# ioboard.net
KiCad netlist of a schematic drawn in EAGLE
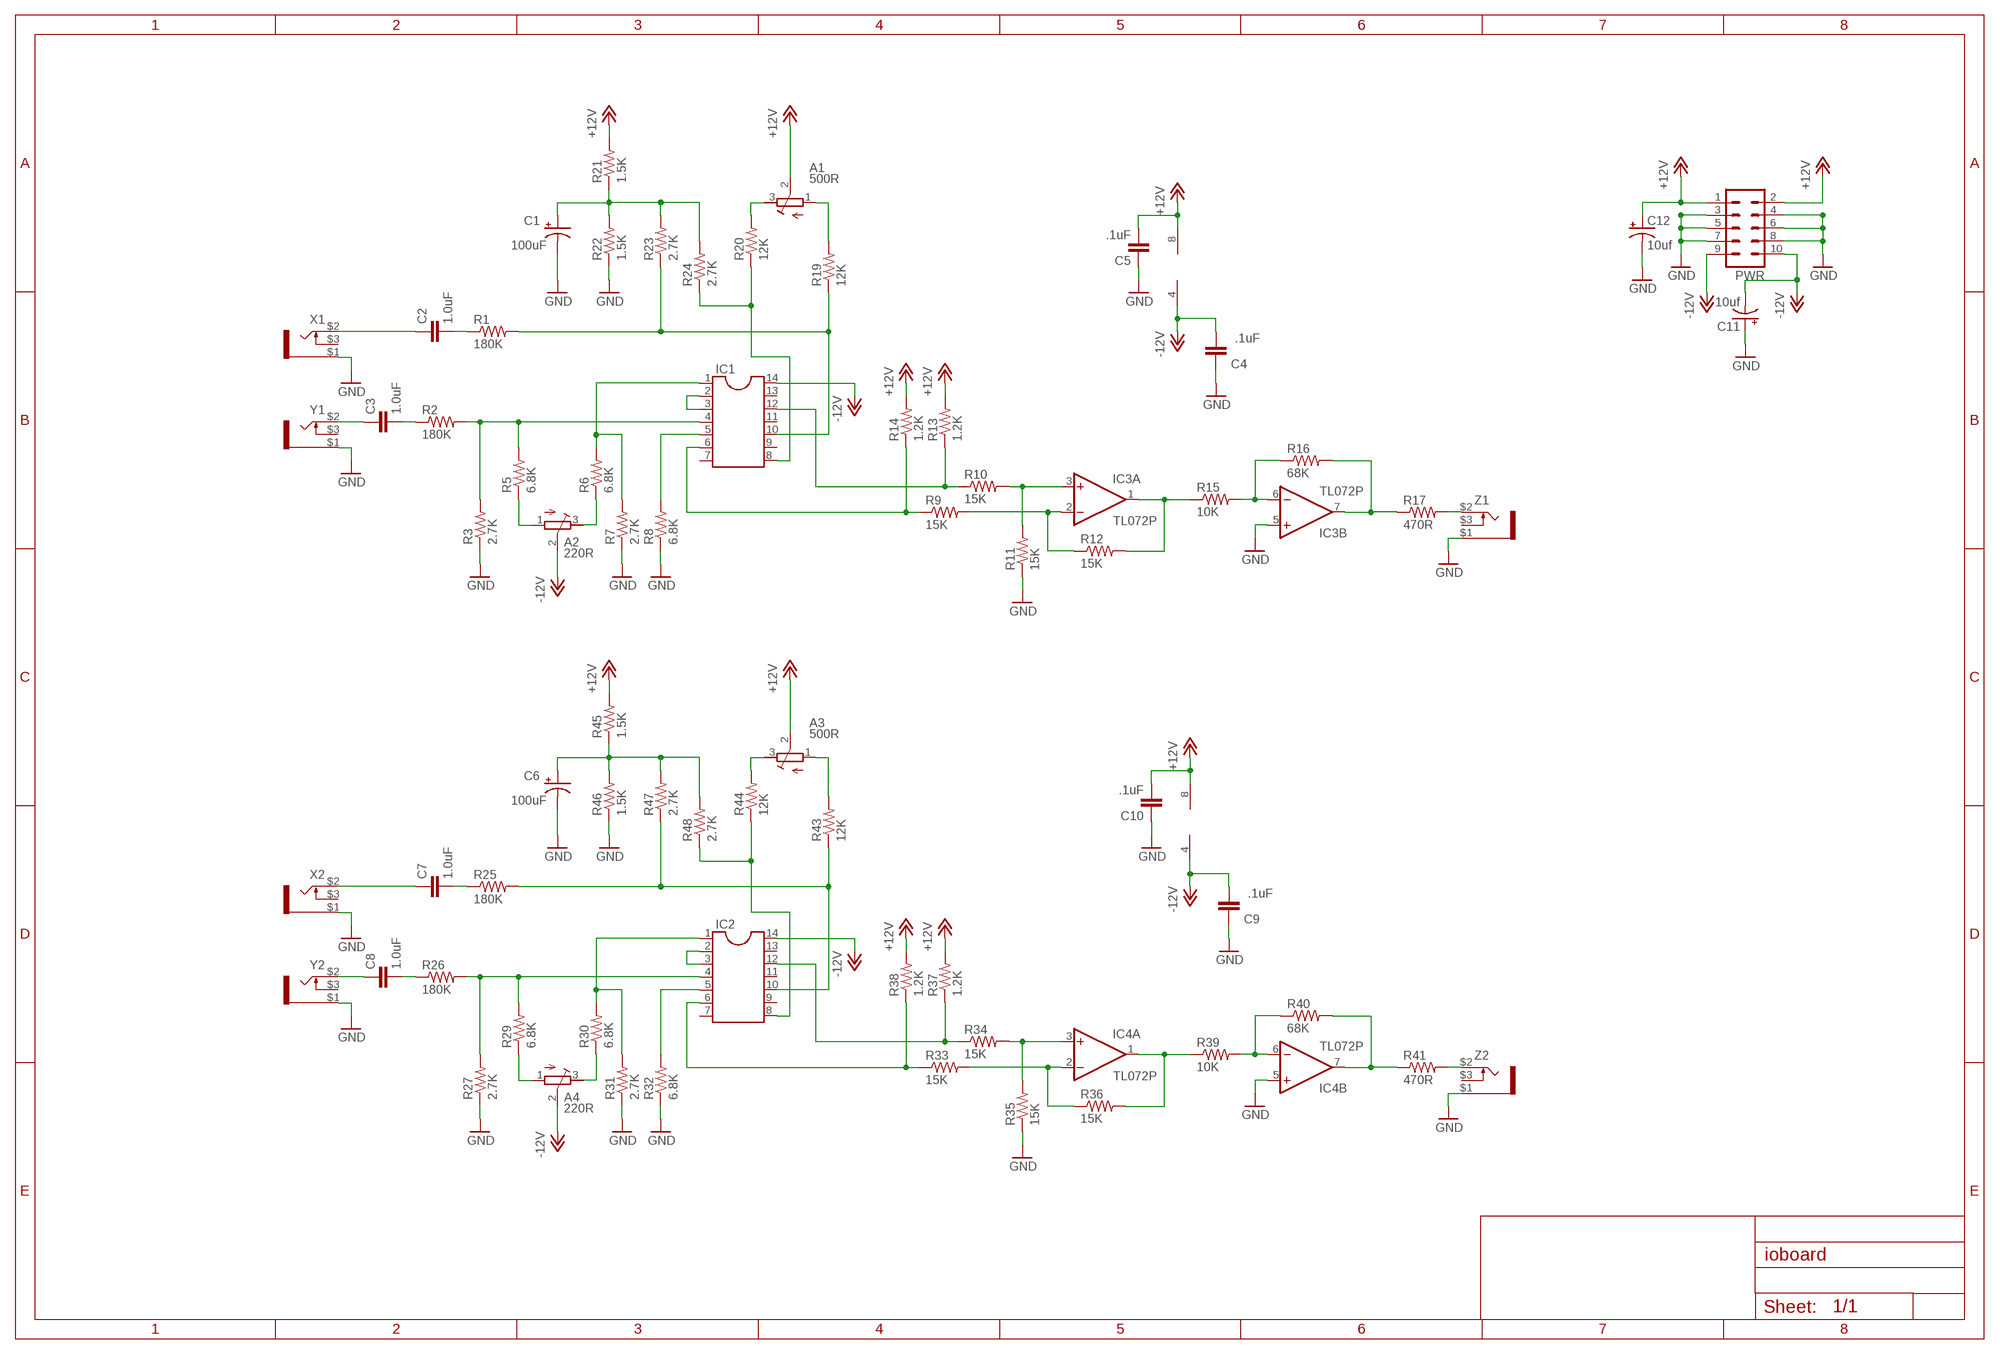
[diagram p0: schematic, sheet 1]

(export (version "E")
  (design (tool "Eeschema 10.0.6"))
  (components
    (comp (ref "A1")
      (value "500R")
      (footprint "eagle-import:RTRIM3296W")
      (libsource (lib "eagle-import") (part "R-TRIMM3296W"))
    )
    (comp (ref "A2")
      (value "220R")
      (footprint "eagle-import:RTRIM3296W")
      (libsource (lib "eagle-import") (part "R-TRIMM3296W"))
    )
    (comp (ref "A3")
      (value "500R")
      (footprint "eagle-import:RTRIM3296W")
      (libsource (lib "eagle-import") (part "R-TRIMM3296W"))
    )
    (comp (ref "A4")
      (value "220R")
      (footprint "eagle-import:RTRIM3296W")
      (libsource (lib "eagle-import") (part "R-TRIMM3296W"))
    )
    (comp (ref "C1")
      (value "100uF")
      (footprint "eagle-import:E2,5-6")
      (libsource (lib "eagle-import") (part "resistor_348_CPOL-USE2.5-6"))
    )
    (comp (ref "C2")
      (value "1.0uF")
      (footprint "eagle-import:C050-024X044")
      (libsource (lib "eagle-import") (part "C-EU050-024X044"))
    )
    (comp (ref "C3")
      (value "1.0uF")
      (footprint "eagle-import:C050-024X044")
      (libsource (lib "eagle-import") (part "C-EU050-024X044"))
    )
    (comp (ref "C4")
      (value ".1uF")
      (footprint "eagle-import:C050-024X044")
      (libsource (lib "eagle-import") (part "C-EU050-024X044"))
    )
    (comp (ref "C5")
      (value ".1uF")
      (footprint "eagle-import:C050-024X044")
      (libsource (lib "eagle-import") (part "C-EU050-024X044"))
    )
    (comp (ref "C6")
      (value "100uF")
      (footprint "eagle-import:E2,5-6")
      (libsource (lib "eagle-import") (part "resistor_348_CPOL-USE2.5-6"))
    )
    (comp (ref "C7")
      (value "1.0uF")
      (footprint "eagle-import:C050-024X044")
      (libsource (lib "eagle-import") (part "C-EU050-024X044"))
    )
    (comp (ref "C8")
      (value "1.0uF")
      (footprint "eagle-import:C050-024X044")
      (libsource (lib "eagle-import") (part "C-EU050-024X044"))
    )
    (comp (ref "C9")
      (value ".1uF")
      (footprint "eagle-import:C050-024X044")
      (libsource (lib "eagle-import") (part "C-EU050-024X044"))
    )
    (comp (ref "C10")
      (value ".1uF")
      (footprint "eagle-import:C050-024X044")
      (libsource (lib "eagle-import") (part "C-EU050-024X044"))
    )
    (comp (ref "C11")
      (value "10uf")
      (footprint "eagle-import:E2,5-5")
      (libsource (lib "eagle-import") (part "CPOL-USE2.5-5"))
    )
    (comp (ref "C12")
      (value "10uf")
      (footprint "eagle-import:E2,5-5")
      (libsource (lib "eagle-import") (part "CPOL-USE2.5-5"))
    )
    (comp (ref "IC1")
      (value "LM1496")
      (footprint "eagle-import:LM1496")
      (libsource (lib "eagle-import") (part "LM1496"))
    )
    (comp (ref "IC2")
      (value "LM1496")
      (footprint "eagle-import:LM1496")
      (libsource (lib "eagle-import") (part "LM1496"))
    )
    (comp (ref "IC3")
      (value "TL072P")
      (footprint "eagle-import:DIL08")
      (libsource (lib "eagle-import") (part "TL072P"))
    )
    (comp (ref "IC4")
      (value "TL072P")
      (footprint "eagle-import:DIL08")
      (libsource (lib "eagle-import") (part "TL072P"))
    )
    (comp (ref "PWR")
      (value "ML10")
      (footprint "eagle-import:ML10")
      (libsource (lib "eagle-import") (part "ML10"))
    )
    (comp (ref "R1")
      (value "180K")
      (footprint "eagle-import:0207_7")
      (libsource (lib "eagle-import") (part "R-US_0207/7"))
    )
    (comp (ref "R2")
      (value "180K")
      (footprint "eagle-import:0207_7")
      (libsource (lib "eagle-import") (part "R-US_0207/7"))
    )
    (comp (ref "R3")
      (value "2.7K")
      (footprint "eagle-import:0207_7")
      (libsource (lib "eagle-import") (part "R-US_0207/7"))
    )
    (comp (ref "R5")
      (value "6.8K")
      (footprint "eagle-import:0207_7")
      (libsource (lib "eagle-import") (part "R-US_0207/7"))
    )
    (comp (ref "R6")
      (value "6.8K")
      (footprint "eagle-import:0207_7")
      (libsource (lib "eagle-import") (part "R-US_0207/7"))
    )
    (comp (ref "R7")
      (value "2.7K")
      (footprint "eagle-import:0207_7")
      (libsource (lib "eagle-import") (part "R-US_0207/7"))
    )
    (comp (ref "R8")
      (value "6.8K")
      (footprint "eagle-import:0207_7")
      (libsource (lib "eagle-import") (part "R-US_0207/7"))
    )
    (comp (ref "R9")
      (value "15K")
      (footprint "eagle-import:0207_7")
      (libsource (lib "eagle-import") (part "R-US_0207/7"))
    )
    (comp (ref "R10")
      (value "15K")
      (footprint "eagle-import:0207_7")
      (libsource (lib "eagle-import") (part "R-US_0207/7"))
    )
    (comp (ref "R11")
      (value "15K")
      (footprint "eagle-import:0207_7")
      (libsource (lib "eagle-import") (part "R-US_0207/7"))
    )
    (comp (ref "R12")
      (value "15K")
      (footprint "eagle-import:0207_7")
      (libsource (lib "eagle-import") (part "R-US_0207/7"))
    )
    (comp (ref "R13")
      (value "1.2K")
      (footprint "eagle-import:0207_7")
      (libsource (lib "eagle-import") (part "R-US_0207/7"))
    )
    (comp (ref "R14")
      (value "1.2K")
      (footprint "eagle-import:0207_7")
      (libsource (lib "eagle-import") (part "R-US_0207/7"))
    )
    (comp (ref "R15")
      (value "10K")
      (footprint "eagle-import:0207_7")
      (libsource (lib "eagle-import") (part "R-US_0207/7"))
    )
    (comp (ref "R16")
      (value "68K")
      (footprint "eagle-import:0207_7")
      (libsource (lib "eagle-import") (part "R-US_0207/7"))
    )
    (comp (ref "R17")
      (value "470R")
      (footprint "eagle-import:0207_7")
      (libsource (lib "eagle-import") (part "R-US_0207/7"))
    )
    (comp (ref "R19")
      (value "12K")
      (footprint "eagle-import:0207_7")
      (libsource (lib "eagle-import") (part "R-US_0207/7"))
    )
    (comp (ref "R20")
      (value "12K")
      (footprint "eagle-import:0207_7")
      (libsource (lib "eagle-import") (part "R-US_0207/7"))
    )
    (comp (ref "R21")
      (value "1.5K")
      (footprint "eagle-import:0207_7")
      (libsource (lib "eagle-import") (part "R-US_0207/7"))
    )
    (comp (ref "R22")
      (value "1.5K")
      (footprint "eagle-import:0207_7")
      (libsource (lib "eagle-import") (part "R-US_0207/7"))
    )
    (comp (ref "R23")
      (value "2.7K")
      (footprint "eagle-import:0207_7")
      (libsource (lib "eagle-import") (part "R-US_0207/7"))
    )
    (comp (ref "R24")
      (value "2.7K")
      (footprint "eagle-import:0207_7")
      (libsource (lib "eagle-import") (part "R-US_0207/7"))
    )
    (comp (ref "R25")
      (value "180K")
      (footprint "eagle-import:0207_7")
      (libsource (lib "eagle-import") (part "R-US_0207/7"))
    )
    (comp (ref "R26")
      (value "180K")
      (footprint "eagle-import:0207_7")
      (libsource (lib "eagle-import") (part "R-US_0207/7"))
    )
    (comp (ref "R27")
      (value "2.7K")
      (footprint "eagle-import:0207_7")
      (libsource (lib "eagle-import") (part "R-US_0207/7"))
    )
    (comp (ref "R29")
      (value "6.8K")
      (footprint "eagle-import:0207_7")
      (libsource (lib "eagle-import") (part "R-US_0207/7"))
    )
    (comp (ref "R30")
      (value "6.8K")
      (footprint "eagle-import:0207_7")
      (libsource (lib "eagle-import") (part "R-US_0207/7"))
    )
    (comp (ref "R31")
      (value "2.7K")
      (footprint "eagle-import:0207_7")
      (libsource (lib "eagle-import") (part "R-US_0207/7"))
    )
    (comp (ref "R32")
      (value "6.8K")
      (footprint "eagle-import:0207_7")
      (libsource (lib "eagle-import") (part "R-US_0207/7"))
    )
    (comp (ref "R33")
      (value "15K")
      (footprint "eagle-import:0207_7")
      (libsource (lib "eagle-import") (part "R-US_0207/7"))
    )
    (comp (ref "R34")
      (value "15K")
      (footprint "eagle-import:0207_7")
      (libsource (lib "eagle-import") (part "R-US_0207/7"))
    )
    (comp (ref "R35")
      (value "15K")
      (footprint "eagle-import:0207_7")
      (libsource (lib "eagle-import") (part "R-US_0207/7"))
    )
    (comp (ref "R36")
      (value "15K")
      (footprint "eagle-import:0207_7")
      (libsource (lib "eagle-import") (part "R-US_0207/7"))
    )
    (comp (ref "R37")
      (value "1.2K")
      (footprint "eagle-import:0207_7")
      (libsource (lib "eagle-import") (part "R-US_0207/7"))
    )
    (comp (ref "R38")
      (value "1.2K")
      (footprint "eagle-import:0207_7")
      (libsource (lib "eagle-import") (part "R-US_0207/7"))
    )
    (comp (ref "R39")
      (value "10K")
      (footprint "eagle-import:0207_7")
      (libsource (lib "eagle-import") (part "R-US_0207/7"))
    )
    (comp (ref "R40")
      (value "68K")
      (footprint "eagle-import:0207_7")
      (libsource (lib "eagle-import") (part "R-US_0207/7"))
    )
    (comp (ref "R41")
      (value "470R")
      (footprint "eagle-import:0207_7")
      (libsource (lib "eagle-import") (part "R-US_0207/7"))
    )
    (comp (ref "R43")
      (value "12K")
      (footprint "eagle-import:0207_7")
      (libsource (lib "eagle-import") (part "R-US_0207/7"))
    )
    (comp (ref "R44")
      (value "12K")
      (footprint "eagle-import:0207_7")
      (libsource (lib "eagle-import") (part "R-US_0207/7"))
    )
    (comp (ref "R45")
      (value "1.5K")
      (footprint "eagle-import:0207_7")
      (libsource (lib "eagle-import") (part "R-US_0207/7"))
    )
    (comp (ref "R46")
      (value "1.5K")
      (footprint "eagle-import:0207_7")
      (libsource (lib "eagle-import") (part "R-US_0207/7"))
    )
    (comp (ref "R47")
      (value "2.7K")
      (footprint "eagle-import:0207_7")
      (libsource (lib "eagle-import") (part "R-US_0207/7"))
    )
    (comp (ref "R48")
      (value "2.7K")
      (footprint "eagle-import:0207_7")
      (libsource (lib "eagle-import") (part "R-US_0207/7"))
    )
    (comp (ref "X1")
      (value "PJ-323PJ-323")
      (footprint "eagle-import:PJ-323")
      (libsource (lib "eagle-import") (part "PJ-323PJ-323"))
    )
    (comp (ref "X2")
      (value "PJ-323PJ-323")
      (footprint "eagle-import:PJ-323")
      (libsource (lib "eagle-import") (part "PJ-323PJ-323"))
    )
    (comp (ref "Y1")
      (value "PJ-323PJ-323")
      (footprint "eagle-import:PJ-323")
      (libsource (lib "eagle-import") (part "PJ-323PJ-323"))
    )
    (comp (ref "Y2")
      (value "PJ-323PJ-323")
      (footprint "eagle-import:PJ-323")
      (libsource (lib "eagle-import") (part "PJ-323PJ-323"))
    )
    (comp (ref "Z1")
      (value "PJ-323PJ-323")
      (footprint "eagle-import:PJ-323")
      (libsource (lib "eagle-import") (part "PJ-323PJ-323"))
    )
    (comp (ref "Z2")
      (value "PJ-323PJ-323")
      (footprint "eagle-import:PJ-323")
      (libsource (lib "eagle-import") (part "PJ-323PJ-323"))
    )
  )
  (nets
    (net (code "1") (name "+12V") (class "Default")
      (node (ref "A1") (pin "2") (pinfunction "S_2") (pintype "passive"))
      (node (ref "A3") (pin "2") (pinfunction "S_2") (pintype "passive"))
      (node (ref "C10") (pin "2") (pinfunction "2_2") (pintype "passive"))
      (node (ref "C12") (pin "+") (pinfunction "+_+") (pintype "passive"))
      (node (ref "C5") (pin "2") (pinfunction "2_2") (pintype "passive"))
      (node (ref "IC3") (pin "8") (pinfunction "V+_8") (pintype "power_in"))
      (node (ref "IC4") (pin "8") (pinfunction "V+_8") (pintype "power_in"))
      (node (ref "PWR") (pin "1") (pinfunction "1_1") (pintype "passive"))
      (node (ref "PWR") (pin "2") (pinfunction "2_2") (pintype "passive"))
      (node (ref "R13") (pin "2") (pinfunction "2_2") (pintype "passive"))
      (node (ref "R14") (pin "2") (pinfunction "2_2") (pintype "passive"))
      (node (ref "R21") (pin "2") (pinfunction "2_2") (pintype "passive"))
      (node (ref "R37") (pin "2") (pinfunction "2_2") (pintype "passive"))
      (node (ref "R38") (pin "2") (pinfunction "2_2") (pintype "passive"))
      (node (ref "R45") (pin "2") (pinfunction "2_2") (pintype "passive"))
    )
    (net (code "2") (name "-12V") (class "Default")
      (node (ref "A2") (pin "2") (pinfunction "S_2") (pintype "passive"))
      (node (ref "A4") (pin "2") (pinfunction "S_2") (pintype "passive"))
      (node (ref "C11") (pin "-") (pinfunction "-_-") (pintype "passive"))
      (node (ref "C4") (pin "2") (pinfunction "2_2") (pintype "passive"))
      (node (ref "C9") (pin "2") (pinfunction "2_2") (pintype "passive"))
      (node (ref "IC1") (pin "14") (pinfunction "14_14") (pintype "passive"))
      (node (ref "IC2") (pin "14") (pinfunction "14_14") (pintype "passive"))
      (node (ref "IC3") (pin "4") (pinfunction "V-_4") (pintype "power_in"))
      (node (ref "IC4") (pin "4") (pinfunction "V-_4") (pintype "power_in"))
      (node (ref "PWR") (pin "10") (pinfunction "10_10") (pintype "passive"))
      (node (ref "PWR") (pin "9") (pinfunction "9_9") (pintype "passive"))
    )
    (net (code "3") (name "GND") (class "Default")
      (node (ref "C1") (pin "-") (pinfunction "-_-") (pintype "passive"))
      (node (ref "C10") (pin "1") (pinfunction "1_1") (pintype "passive"))
      (node (ref "C11") (pin "+") (pinfunction "+_+") (pintype "passive"))
      (node (ref "C12") (pin "-") (pinfunction "-_-") (pintype "passive"))
      (node (ref "C4") (pin "1") (pinfunction "1_1") (pintype "passive"))
      (node (ref "C5") (pin "1") (pinfunction "1_1") (pintype "passive"))
      (node (ref "C6") (pin "-") (pinfunction "-_-") (pintype "passive"))
      (node (ref "C9") (pin "1") (pinfunction "1_1") (pintype "passive"))
      (node (ref "IC3") (pin "5") (pinfunction "+IN_5") (pintype "input"))
      (node (ref "IC4") (pin "5") (pinfunction "+IN_5") (pintype "input"))
      (node (ref "PWR") (pin "3") (pinfunction "3_3") (pintype "passive"))
      (node (ref "PWR") (pin "4") (pinfunction "4_4") (pintype "passive"))
      (node (ref "PWR") (pin "5") (pinfunction "5_5") (pintype "passive"))
      (node (ref "PWR") (pin "6") (pinfunction "6_6") (pintype "passive"))
      (node (ref "PWR") (pin "7") (pinfunction "7_7") (pintype "passive"))
      (node (ref "PWR") (pin "8") (pinfunction "8_8") (pintype "passive"))
      (node (ref "R11") (pin "1") (pinfunction "1_1") (pintype "passive"))
      (node (ref "R22") (pin "1") (pinfunction "1_1") (pintype "passive"))
      (node (ref "R27") (pin "1") (pinfunction "1_1") (pintype "passive"))
      (node (ref "R3") (pin "1") (pinfunction "1_1") (pintype "passive"))
      (node (ref "R31") (pin "1") (pinfunction "1_1") (pintype "passive"))
      (node (ref "R32") (pin "1") (pinfunction "1_1") (pintype "passive"))
      (node (ref "R35") (pin "1") (pinfunction "1_1") (pintype "passive"))
      (node (ref "R46") (pin "1") (pinfunction "1_1") (pintype "passive"))
      (node (ref "R7") (pin "1") (pinfunction "1_1") (pintype "passive"))
      (node (ref "R8") (pin "1") (pinfunction "1_1") (pintype "passive"))
      (node (ref "X1") (pin "$1") (pinfunction "3_$1") (pintype "passive"))
      (node (ref "X2") (pin "$1") (pinfunction "3_$1") (pintype "passive"))
      (node (ref "Y1") (pin "$1") (pinfunction "3_$1") (pintype "passive"))
      (node (ref "Y2") (pin "$1") (pinfunction "3_$1") (pintype "passive"))
      (node (ref "Z1") (pin "$1") (pinfunction "3_$1") (pintype "passive"))
      (node (ref "Z2") (pin "$1") (pinfunction "3_$1") (pintype "passive"))
    )
    (net (code "4") (name "Net-(A1-A)") (class "Default")
      (node (ref "A1") (pin "1") (pinfunction "A_1") (pintype "passive"))
      (node (ref "R19") (pin "2") (pinfunction "2_2") (pintype "passive"))
    )
    (net (code "5") (name "Net-(A1-E)") (class "Default")
      (node (ref "A1") (pin "3") (pinfunction "E_3") (pintype "passive"))
      (node (ref "R20") (pin "2") (pinfunction "2_2") (pintype "passive"))
    )
    (net (code "6") (name "Net-(A2-A)") (class "Default")
      (node (ref "A2") (pin "1") (pinfunction "A_1") (pintype "passive"))
      (node (ref "R5") (pin "1") (pinfunction "1_1") (pintype "passive"))
    )
    (net (code "7") (name "Net-(A2-E)") (class "Default")
      (node (ref "A2") (pin "3") (pinfunction "E_3") (pintype "passive"))
      (node (ref "R6") (pin "1") (pinfunction "1_1") (pintype "passive"))
    )
    (net (code "8") (name "Net-(A3-A)") (class "Default")
      (node (ref "A3") (pin "1") (pinfunction "A_1") (pintype "passive"))
      (node (ref "R43") (pin "2") (pinfunction "2_2") (pintype "passive"))
    )
    (net (code "9") (name "Net-(A3-E)") (class "Default")
      (node (ref "A3") (pin "3") (pinfunction "E_3") (pintype "passive"))
      (node (ref "R44") (pin "2") (pinfunction "2_2") (pintype "passive"))
    )
    (net (code "10") (name "Net-(A4-A)") (class "Default")
      (node (ref "A4") (pin "1") (pinfunction "A_1") (pintype "passive"))
      (node (ref "R29") (pin "1") (pinfunction "1_1") (pintype "passive"))
    )
    (net (code "11") (name "Net-(A4-E)") (class "Default")
      (node (ref "A4") (pin "3") (pinfunction "E_3") (pintype "passive"))
      (node (ref "R30") (pin "1") (pinfunction "1_1") (pintype "passive"))
    )
    (net (code "12") (name "Net-(C1-Pad+)") (class "Default")
      (node (ref "C1") (pin "+") (pinfunction "+_+") (pintype "passive"))
      (node (ref "R21") (pin "1") (pinfunction "1_1") (pintype "passive"))
      (node (ref "R22") (pin "2") (pinfunction "2_2") (pintype "passive"))
      (node (ref "R23") (pin "2") (pinfunction "2_2") (pintype "passive"))
      (node (ref "R24") (pin "2") (pinfunction "2_2") (pintype "passive"))
    )
    (net (code "13") (name "Net-(C2-Pad2)") (class "Default")
      (node (ref "C2") (pin "2") (pinfunction "2_2") (pintype "passive"))
      (node (ref "R1") (pin "1") (pinfunction "1_1") (pintype "passive"))
    )
    (net (code "14") (name "Net-(C3-Pad2)") (class "Default")
      (node (ref "C3") (pin "2") (pinfunction "2_2") (pintype "passive"))
      (node (ref "R2") (pin "1") (pinfunction "1_1") (pintype "passive"))
    )
    (net (code "15") (name "Net-(C6-Pad+)") (class "Default")
      (node (ref "C6") (pin "+") (pinfunction "+_+") (pintype "passive"))
      (node (ref "R45") (pin "1") (pinfunction "1_1") (pintype "passive"))
      (node (ref "R46") (pin "2") (pinfunction "2_2") (pintype "passive"))
      (node (ref "R47") (pin "2") (pinfunction "2_2") (pintype "passive"))
      (node (ref "R48") (pin "2") (pinfunction "2_2") (pintype "passive"))
    )
    (net (code "16") (name "Net-(C7-Pad2)") (class "Default")
      (node (ref "C7") (pin "2") (pinfunction "2_2") (pintype "passive"))
      (node (ref "R25") (pin "1") (pinfunction "1_1") (pintype "passive"))
    )
    (net (code "17") (name "Net-(C8-Pad2)") (class "Default")
      (node (ref "C8") (pin "2") (pinfunction "2_2") (pintype "passive"))
      (node (ref "R26") (pin "1") (pinfunction "1_1") (pintype "passive"))
    )
    (net (code "18") (name "Net-(IC1-Pad1)") (class "Default")
      (node (ref "IC1") (pin "1") (pinfunction "1_1") (pintype "passive"))
      (node (ref "R6") (pin "2") (pinfunction "2_2") (pintype "passive"))
      (node (ref "R7") (pin "2") (pinfunction "2_2") (pintype "passive"))
    )
    (net (code "19") (name "Net-(IC1-Pad2)") (class "Default")
      (node (ref "IC1") (pin "2") (pinfunction "2_2") (pintype "passive"))
      (node (ref "IC1") (pin "3") (pinfunction "3_3") (pintype "passive"))
    )
    (net (code "20") (name "Net-(IC1-Pad4)") (class "Default")
      (node (ref "IC1") (pin "4") (pinfunction "4_4") (pintype "passive"))
      (node (ref "R2") (pin "2") (pinfunction "2_2") (pintype "passive"))
      (node (ref "R3") (pin "2") (pinfunction "2_2") (pintype "passive"))
      (node (ref "R5") (pin "2") (pinfunction "2_2") (pintype "passive"))
    )
    (net (code "21") (name "Net-(IC1-Pad5)") (class "Default")
      (node (ref "IC1") (pin "5") (pinfunction "5_5") (pintype "passive"))
      (node (ref "R8") (pin "2") (pinfunction "2_2") (pintype "passive"))
    )
    (net (code "22") (name "Net-(IC1-Pad6)") (class "Default")
      (node (ref "IC1") (pin "6") (pinfunction "6_6") (pintype "passive"))
      (node (ref "R14") (pin "1") (pinfunction "1_1") (pintype "passive"))
      (node (ref "R9") (pin "1") (pinfunction "1_1") (pintype "passive"))
    )
    (net (code "23") (name "Net-(IC1-Pad8)") (class "Default")
      (node (ref "IC1") (pin "8") (pinfunction "8_8") (pintype "passive"))
      (node (ref "R20") (pin "1") (pinfunction "1_1") (pintype "passive"))
      (node (ref "R24") (pin "1") (pinfunction "1_1") (pintype "passive"))
    )
    (net (code "24") (name "Net-(IC1-Pad10)") (class "Default")
      (node (ref "IC1") (pin "10") (pinfunction "10_10") (pintype "passive"))
      (node (ref "R1") (pin "2") (pinfunction "2_2") (pintype "passive"))
      (node (ref "R19") (pin "1") (pinfunction "1_1") (pintype "passive"))
      (node (ref "R23") (pin "1") (pinfunction "1_1") (pintype "passive"))
    )
    (net (code "25") (name "Net-(IC1-Pad12)") (class "Default")
      (node (ref "IC1") (pin "12") (pinfunction "12_12") (pintype "passive"))
      (node (ref "R10") (pin "1") (pinfunction "1_1") (pintype "passive"))
      (node (ref "R13") (pin "1") (pinfunction "1_1") (pintype "passive"))
    )
    (net (code "26") (name "Net-(IC2-Pad1)") (class "Default")
      (node (ref "IC2") (pin "1") (pinfunction "1_1") (pintype "passive"))
      (node (ref "R30") (pin "2") (pinfunction "2_2") (pintype "passive"))
      (node (ref "R31") (pin "2") (pinfunction "2_2") (pintype "passive"))
    )
    (net (code "27") (name "Net-(IC2-Pad2)") (class "Default")
      (node (ref "IC2") (pin "2") (pinfunction "2_2") (pintype "passive"))
      (node (ref "IC2") (pin "3") (pinfunction "3_3") (pintype "passive"))
    )
    (net (code "28") (name "Net-(IC2-Pad4)") (class "Default")
      (node (ref "IC2") (pin "4") (pinfunction "4_4") (pintype "passive"))
      (node (ref "R26") (pin "2") (pinfunction "2_2") (pintype "passive"))
      (node (ref "R27") (pin "2") (pinfunction "2_2") (pintype "passive"))
      (node (ref "R29") (pin "2") (pinfunction "2_2") (pintype "passive"))
    )
    (net (code "29") (name "Net-(IC2-Pad5)") (class "Default")
      (node (ref "IC2") (pin "5") (pinfunction "5_5") (pintype "passive"))
      (node (ref "R32") (pin "2") (pinfunction "2_2") (pintype "passive"))
    )
    (net (code "30") (name "Net-(IC2-Pad6)") (class "Default")
      (node (ref "IC2") (pin "6") (pinfunction "6_6") (pintype "passive"))
      (node (ref "R33") (pin "1") (pinfunction "1_1") (pintype "passive"))
      (node (ref "R38") (pin "1") (pinfunction "1_1") (pintype "passive"))
    )
    (net (code "31") (name "Net-(IC2-Pad8)") (class "Default")
      (node (ref "IC2") (pin "8") (pinfunction "8_8") (pintype "passive"))
      (node (ref "R44") (pin "1") (pinfunction "1_1") (pintype "passive"))
      (node (ref "R48") (pin "1") (pinfunction "1_1") (pintype "passive"))
    )
    (net (code "32") (name "Net-(IC2-Pad10)") (class "Default")
      (node (ref "IC2") (pin "10") (pinfunction "10_10") (pintype "passive"))
      (node (ref "R25") (pin "2") (pinfunction "2_2") (pintype "passive"))
      (node (ref "R43") (pin "1") (pinfunction "1_1") (pintype "passive"))
      (node (ref "R47") (pin "1") (pinfunction "1_1") (pintype "passive"))
    )
    (net (code "33") (name "Net-(IC2-Pad12)") (class "Default")
      (node (ref "IC2") (pin "12") (pinfunction "12_12") (pintype "passive"))
      (node (ref "R34") (pin "1") (pinfunction "1_1") (pintype "passive"))
      (node (ref "R37") (pin "1") (pinfunction "1_1") (pintype "passive"))
    )
    (net (code "34") (name "Net-(IC3A-+IN)") (class "Default")
      (node (ref "IC3") (pin "3") (pinfunction "+IN_3") (pintype "input"))
      (node (ref "R10") (pin "2") (pinfunction "2_2") (pintype "passive"))
      (node (ref "R11") (pin "2") (pinfunction "2_2") (pintype "passive"))
    )
    (net (code "35") (name "Net-(IC3A--IN)") (class "Default")
      (node (ref "IC3") (pin "2") (pinfunction "-IN_2") (pintype "input"))
      (node (ref "R12") (pin "1") (pinfunction "1_1") (pintype "passive"))
      (node (ref "R9") (pin "2") (pinfunction "2_2") (pintype "passive"))
    )
    (net (code "36") (name "Net-(IC3A-OUT)") (class "Default")
      (node (ref "IC3") (pin "1") (pinfunction "OUT_1") (pintype "output"))
      (node (ref "R12") (pin "2") (pinfunction "2_2") (pintype "passive"))
      (node (ref "R15") (pin "1") (pinfunction "1_1") (pintype "passive"))
    )
    (net (code "37") (name "Net-(IC3B--IN)") (class "Default")
      (node (ref "IC3") (pin "6") (pinfunction "-IN_6") (pintype "input"))
      (node (ref "R15") (pin "2") (pinfunction "2_2") (pintype "passive"))
      (node (ref "R16") (pin "1") (pinfunction "1_1") (pintype "passive"))
    )
    (net (code "38") (name "Net-(IC3B-OUT)") (class "Default")
      (node (ref "IC3") (pin "7") (pinfunction "OUT_7") (pintype "output"))
      (node (ref "R16") (pin "2") (pinfunction "2_2") (pintype "passive"))
      (node (ref "R17") (pin "1") (pinfunction "1_1") (pintype "passive"))
    )
    (net (code "39") (name "Net-(IC4A-+IN)") (class "Default")
      (node (ref "IC4") (pin "3") (pinfunction "+IN_3") (pintype "input"))
      (node (ref "R34") (pin "2") (pinfunction "2_2") (pintype "passive"))
      (node (ref "R35") (pin "2") (pinfunction "2_2") (pintype "passive"))
    )
    (net (code "40") (name "Net-(IC4A--IN)") (class "Default")
      (node (ref "IC4") (pin "2") (pinfunction "-IN_2") (pintype "input"))
      (node (ref "R33") (pin "2") (pinfunction "2_2") (pintype "passive"))
      (node (ref "R36") (pin "1") (pinfunction "1_1") (pintype "passive"))
    )
    (net (code "41") (name "Net-(IC4A-OUT)") (class "Default")
      (node (ref "IC4") (pin "1") (pinfunction "OUT_1") (pintype "output"))
      (node (ref "R36") (pin "2") (pinfunction "2_2") (pintype "passive"))
      (node (ref "R39") (pin "1") (pinfunction "1_1") (pintype "passive"))
    )
    (net (code "42") (name "Net-(IC4B--IN)") (class "Default")
      (node (ref "IC4") (pin "6") (pinfunction "-IN_6") (pintype "input"))
      (node (ref "R39") (pin "2") (pinfunction "2_2") (pintype "passive"))
      (node (ref "R40") (pin "1") (pinfunction "1_1") (pintype "passive"))
    )
    (net (code "43") (name "Net-(IC4B-OUT)") (class "Default")
      (node (ref "IC4") (pin "7") (pinfunction "OUT_7") (pintype "output"))
      (node (ref "R40") (pin "2") (pinfunction "2_2") (pintype "passive"))
      (node (ref "R41") (pin "1") (pinfunction "1_1") (pintype "passive"))
    )
    (net (code "44") (name "Net-(X1-1)") (class "Default")
      (node (ref "C2") (pin "1") (pinfunction "1_1") (pintype "passive"))
      (node (ref "X1") (pin "$2") (pinfunction "1_$2") (pintype "passive"))
    )
    (net (code "45") (name "Net-(X2-1)") (class "Default")
      (node (ref "C7") (pin "1") (pinfunction "1_1") (pintype "passive"))
      (node (ref "X2") (pin "$2") (pinfunction "1_$2") (pintype "passive"))
    )
    (net (code "46") (name "Net-(Y1-1)") (class "Default")
      (node (ref "C3") (pin "1") (pinfunction "1_1") (pintype "passive"))
      (node (ref "Y1") (pin "$2") (pinfunction "1_$2") (pintype "passive"))
    )
    (net (code "47") (name "Net-(Y2-1)") (class "Default")
      (node (ref "C8") (pin "1") (pinfunction "1_1") (pintype "passive"))
      (node (ref "Y2") (pin "$2") (pinfunction "1_$2") (pintype "passive"))
    )
    (net (code "48") (name "Net-(Z1-1)") (class "Default")
      (node (ref "R17") (pin "2") (pinfunction "2_2") (pintype "passive"))
      (node (ref "Z1") (pin "$2") (pinfunction "1_$2") (pintype "passive"))
    )
    (net (code "49") (name "Net-(Z2-1)") (class "Default")
      (node (ref "R41") (pin "2") (pinfunction "2_2") (pintype "passive"))
      (node (ref "Z2") (pin "$2") (pinfunction "1_$2") (pintype "passive"))
    )
    (net (code "50") (name "unconnected-(IC1-Pad7)") (class "Default")
      (node (ref "IC1") (pin "7") (pinfunction "7_7") (pintype "passive"))
    )
    (net (code "51") (name "unconnected-(IC1-Pad9)") (class "Default")
      (node (ref "IC1") (pin "9") (pinfunction "9_9") (pintype "passive"))
    )
    (net (code "52") (name "unconnected-(IC1-Pad11)") (class "Default")
      (node (ref "IC1") (pin "11") (pinfunction "11_11") (pintype "passive"))
    )
    (net (code "53") (name "unconnected-(IC1-Pad13)") (class "Default")
      (node (ref "IC1") (pin "13") (pinfunction "13_13") (pintype "passive"))
    )
    (net (code "54") (name "unconnected-(IC2-Pad7)") (class "Default")
      (node (ref "IC2") (pin "7") (pinfunction "7_7") (pintype "passive"))
    )
    (net (code "55") (name "unconnected-(IC2-Pad9)") (class "Default")
      (node (ref "IC2") (pin "9") (pinfunction "9_9") (pintype "passive"))
    )
    (net (code "56") (name "unconnected-(IC2-Pad11)") (class "Default")
      (node (ref "IC2") (pin "11") (pinfunction "11_11") (pintype "passive"))
    )
    (net (code "57") (name "unconnected-(IC2-Pad13)") (class "Default")
      (node (ref "IC2") (pin "13") (pinfunction "13_13") (pintype "passive"))
    )
    (net (code "58") (name "unconnected-(X1-2-Pad$3)") (class "Default")
      (node (ref "X1") (pin "$3") (pinfunction "2_$3") (pintype "passive"))
    )
    (net (code "59") (name "unconnected-(X2-2-Pad$3)") (class "Default")
      (node (ref "X2") (pin "$3") (pinfunction "2_$3") (pintype "passive"))
    )
    (net (code "60") (name "unconnected-(Y1-2-Pad$3)") (class "Default")
      (node (ref "Y1") (pin "$3") (pinfunction "2_$3") (pintype "passive"))
    )
    (net (code "61") (name "unconnected-(Y2-2-Pad$3)") (class "Default")
      (node (ref "Y2") (pin "$3") (pinfunction "2_$3") (pintype "passive"))
    )
    (net (code "62") (name "unconnected-(Z1-2-Pad$3)") (class "Default")
      (node (ref "Z1") (pin "$3") (pinfunction "2_$3") (pintype "passive"))
    )
    (net (code "63") (name "unconnected-(Z2-2-Pad$3)") (class "Default")
      (node (ref "Z2") (pin "$3") (pinfunction "2_$3") (pintype "passive"))
    )
  )
)
